# Power_MPU.net
KiCad netlist of a schematic drawn in Altium Designer
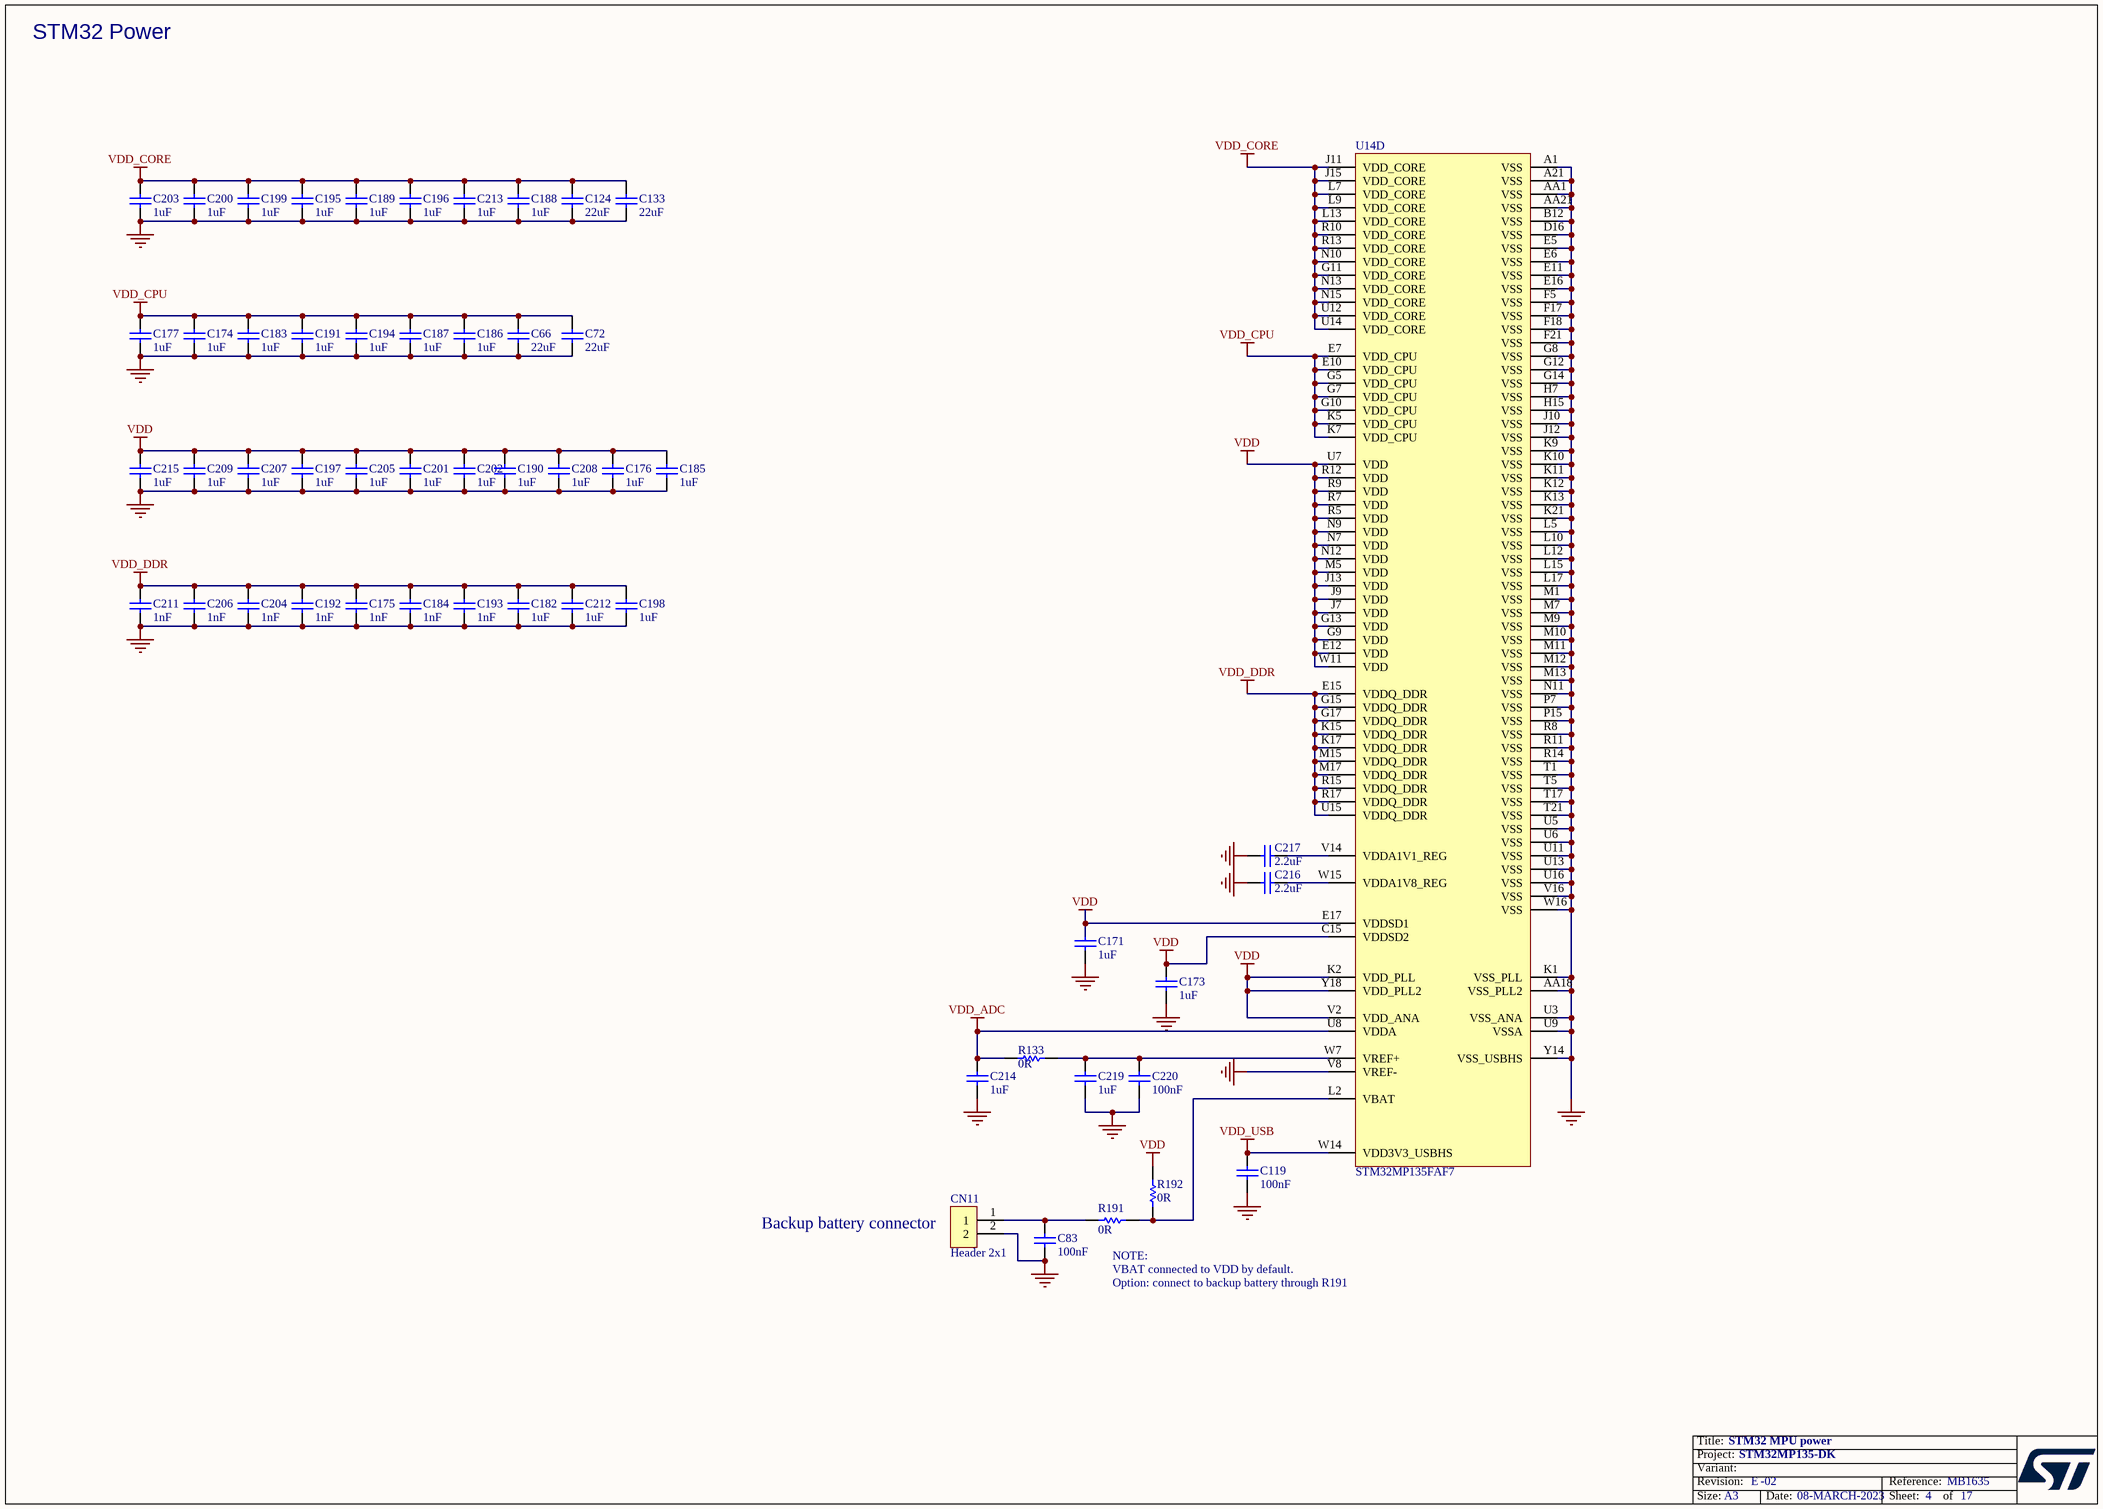
[diagram p0: Power_MPU.SchDoc]

(export (version "E")
  (design (tool "Eeschema 10.0.6"))
  (components
    (comp (ref "C66")
      (value "22uF")
      (footprint "C0603")
      (description "Capacitor, MLCC, 22uF, 6V3, X5R, +/-20%, 0603, T=0.8mm")
      (fields (field (name "INTERNAL_PART_NUMBER") "MCD-00100") (field (name "MANUFACTURER") "MURATA"))
      (libsource (lib "MCD_PARTS_database") (part "Capacitor"))
    )
    (comp (ref "C72")
      (value "22uF")
      (footprint "C0603")
      (description "Capacitor, MLCC, 22uF, 6V3, X5R, +/-20%, 0603, T=0.8mm")
      (fields (field (name "INTERNAL_PART_NUMBER") "MCD-00100") (field (name "MANUFACTURER") "MURATA"))
      (libsource (lib "MCD_PARTS_database") (part "Capacitor"))
    )
    (comp (ref "C83")
      (value "100nF")
      (footprint "C0402")
      (description "Capacitor, MLCC, 100nF, 16V, X7R, +/-10%, 0402, T=0.5mm")
      (fields
        (field (name "INTERNAL_PART_NUMBER") "MCD-00006")
        (field (name "MANUFACTURER_PART_NUMBER") "CC0402KRX7R7BB104")
      )
      (libsource (lib "MCD_PARTS_database") (part "Capacitor"))
    )
    (comp (ref "C119")
      (value "100nF")
      (footprint "C0402")
      (description "Capacitor, MLCC, 100nF, 16V, X7R, +/-10%, 0402, T=0.5mm")
      (fields
        (field (name "INTERNAL_PART_NUMBER") "MCD-00006")
        (field (name "MANUFACTURER_PART_NUMBER") "CC0402KRX7R7BB104")
      )
      (libsource (lib "MCD_PARTS_database") (part "Capacitor"))
    )
    (comp (ref "C124")
      (value "22uF")
      (footprint "C0603")
      (description "Capacitor, MLCC, 22uF, 6V3, X5R, +/-20%, 0603, T=0.8mm")
      (fields (field (name "INTERNAL_PART_NUMBER") "MCD-00100") (field (name "MANUFACTURER") "MURATA"))
      (libsource (lib "MCD_PARTS_database") (part "Capacitor"))
    )
    (comp (ref "C133")
      (value "22uF")
      (footprint "C0603")
      (description "Capacitor, MLCC, 22uF, 6V3, X5R, +/-20%, 0603, T=0.8mm")
      (fields (field (name "INTERNAL_PART_NUMBER") "MCD-00100") (field (name "MANUFACTURER") "MURATA"))
      (libsource (lib "MCD_PARTS_database") (part "Capacitor"))
    )
    (comp (ref "C171")
      (value "1uF")
      (footprint "C0201_MURATA_GRM033_H0P3")
      (description "Capacitor, MLCC, 1uF, 6.3V, X5R, +/-20%, 0201, T=0,3mm")
      (fields (field (name "INTERNAL_PART_NUMBER") "MCD-02377") (field (name "MANUFACTURER") "MURATA"))
      (libsource (lib "MCD_PARTS_database") (part "Capacitor"))
    )
    (comp (ref "C173")
      (value "1uF")
      (footprint "C0201_MURATA_GRM033_H0P3")
      (description "Capacitor, MLCC, 1uF, 6.3V, X5R, +/-20%, 0201, T=0,3mm")
      (fields (field (name "INTERNAL_PART_NUMBER") "MCD-02377") (field (name "MANUFACTURER") "MURATA"))
      (libsource (lib "MCD_PARTS_database") (part "Capacitor"))
    )
    (comp (ref "C174")
      (value "1uF")
      (footprint "C0201_MURATA_GRM033_H0P3")
      (description "Capacitor, MLCC, 1uF, 6.3V, X5R, +/-20%, 0201, T=0,3mm")
      (fields (field (name "INTERNAL_PART_NUMBER") "MCD-02377") (field (name "MANUFACTURER") "MURATA"))
      (libsource (lib "MCD_PARTS_database") (part "Capacitor"))
    )
    (comp (ref "C175")
      (value "1nF")
      (footprint "C0201_MURATA_GRM033_H0P3")
      (description "Capacitor, MLCC, 1nF, 25V, X7R,+/-5%, 0201,T=0.3mm")
      (fields (field (name "INTERNAL_PART_NUMBER") "MCD-01729") (field (name "MANUFACTURER") "MURATA"))
      (libsource (lib "MCD_PARTS_database") (part "Capacitor"))
    )
    (comp (ref "C176")
      (value "1uF")
      (footprint "C0201_MURATA_GRM033_H0P3")
      (description "Capacitor, MLCC, 1uF, 6.3V, X5R, +/-20%, 0201, T=0,3mm")
      (fields (field (name "INTERNAL_PART_NUMBER") "MCD-02377") (field (name "MANUFACTURER") "MURATA"))
      (libsource (lib "MCD_PARTS_database") (part "Capacitor"))
    )
    (comp (ref "C177")
      (value "1uF")
      (footprint "C0201_MURATA_GRM033_H0P3")
      (description "Capacitor, MLCC, 1uF, 6.3V, X5R, +/-20%, 0201, T=0,3mm")
      (fields (field (name "INTERNAL_PART_NUMBER") "MCD-02377") (field (name "MANUFACTURER") "MURATA"))
      (libsource (lib "MCD_PARTS_database") (part "Capacitor"))
    )
    (comp (ref "C182")
      (value "1uF")
      (footprint "C0201_MURATA_GRM033_H0P3")
      (description "Capacitor, MLCC, 1uF, 6.3V, X5R, +/-20%, 0201, T=0,3mm")
      (fields (field (name "INTERNAL_PART_NUMBER") "MCD-02377") (field (name "MANUFACTURER") "MURATA"))
      (libsource (lib "MCD_PARTS_database") (part "Capacitor"))
    )
    (comp (ref "C183")
      (value "1uF")
      (footprint "C0201_MURATA_GRM033_H0P3")
      (description "Capacitor, MLCC, 1uF, 6.3V, X5R, +/-20%, 0201, T=0,3mm")
      (fields (field (name "INTERNAL_PART_NUMBER") "MCD-02377") (field (name "MANUFACTURER") "MURATA"))
      (libsource (lib "MCD_PARTS_database") (part "Capacitor"))
    )
    (comp (ref "C184")
      (value "1nF")
      (footprint "C0201_MURATA_GRM033_H0P3")
      (description "Capacitor, MLCC, 1nF, 25V, X7R,+/-5%, 0201,T=0.3mm")
      (fields (field (name "INTERNAL_PART_NUMBER") "MCD-01729") (field (name "MANUFACTURER") "MURATA"))
      (libsource (lib "MCD_PARTS_database") (part "Capacitor"))
    )
    (comp (ref "C185")
      (value "1uF")
      (footprint "C0201_MURATA_GRM033_H0P3")
      (description "Capacitor, MLCC, 1uF, 6.3V, X5R, +/-20%, 0201, T=0,3mm")
      (fields (field (name "INTERNAL_PART_NUMBER") "MCD-02377") (field (name "MANUFACTURER") "MURATA"))
      (libsource (lib "MCD_PARTS_database") (part "Capacitor"))
    )
    (comp (ref "C186")
      (value "1uF")
      (footprint "C0201_MURATA_GRM033_H0P3")
      (description "Capacitor, MLCC, 1uF, 6.3V, X5R, +/-20%, 0201, T=0,3mm")
      (fields (field (name "INTERNAL_PART_NUMBER") "MCD-02377") (field (name "MANUFACTURER") "MURATA"))
      (libsource (lib "MCD_PARTS_database") (part "Capacitor"))
    )
    (comp (ref "C187")
      (value "1uF")
      (footprint "C0201_MURATA_GRM033_H0P3")
      (description "Capacitor, MLCC, 1uF, 6.3V, X5R, +/-20%, 0201, T=0,3mm")
      (fields (field (name "INTERNAL_PART_NUMBER") "MCD-02377") (field (name "MANUFACTURER") "MURATA"))
      (libsource (lib "MCD_PARTS_database") (part "Capacitor"))
    )
    (comp (ref "C188")
      (value "1uF")
      (footprint "C0201_MURATA_GRM033_H0P3")
      (description "Capacitor, MLCC, 1uF, 6.3V, X5R, +/-20%, 0201, T=0,3mm")
      (fields (field (name "INTERNAL_PART_NUMBER") "MCD-02377") (field (name "MANUFACTURER") "MURATA"))
      (libsource (lib "MCD_PARTS_database") (part "Capacitor"))
    )
    (comp (ref "C189")
      (value "1uF")
      (footprint "C0201_MURATA_GRM033_H0P3")
      (description "Capacitor, MLCC, 1uF, 6.3V, X5R, +/-20%, 0201, T=0,3mm")
      (fields (field (name "INTERNAL_PART_NUMBER") "MCD-02377") (field (name "MANUFACTURER") "MURATA"))
      (libsource (lib "MCD_PARTS_database") (part "Capacitor"))
    )
    (comp (ref "C190")
      (value "1uF")
      (footprint "C0201_MURATA_GRM033_H0P3")
      (description "Capacitor, MLCC, 1uF, 6.3V, X5R, +/-20%, 0201, T=0,3mm")
      (fields (field (name "INTERNAL_PART_NUMBER") "MCD-02377") (field (name "MANUFACTURER") "MURATA"))
      (libsource (lib "MCD_PARTS_database") (part "Capacitor"))
    )
    (comp (ref "C191")
      (value "1uF")
      (footprint "C0201_MURATA_GRM033_H0P3")
      (description "Capacitor, MLCC, 1uF, 6.3V, X5R, +/-20%, 0201, T=0,3mm")
      (fields (field (name "INTERNAL_PART_NUMBER") "MCD-02377") (field (name "MANUFACTURER") "MURATA"))
      (libsource (lib "MCD_PARTS_database") (part "Capacitor"))
    )
    (comp (ref "C192")
      (value "1nF")
      (footprint "C0201_MURATA_GRM033_H0P3")
      (description "Capacitor, MLCC, 1nF, 25V, X7R,+/-5%, 0201,T=0.3mm")
      (fields (field (name "INTERNAL_PART_NUMBER") "MCD-01729") (field (name "MANUFACTURER") "MURATA"))
      (libsource (lib "MCD_PARTS_database") (part "Capacitor"))
    )
    (comp (ref "C193")
      (value "1nF")
      (footprint "C0201_MURATA_GRM033_H0P3")
      (description "Capacitor, MLCC, 1nF, 25V, X7R,+/-5%, 0201,T=0.3mm")
      (fields (field (name "INTERNAL_PART_NUMBER") "MCD-01729") (field (name "MANUFACTURER") "MURATA"))
      (libsource (lib "MCD_PARTS_database") (part "Capacitor"))
    )
    (comp (ref "C194")
      (value "1uF")
      (footprint "C0201_MURATA_GRM033_H0P3")
      (description "Capacitor, MLCC, 1uF, 6.3V, X5R, +/-20%, 0201, T=0,3mm")
      (fields (field (name "INTERNAL_PART_NUMBER") "MCD-02377") (field (name "MANUFACTURER") "MURATA"))
      (libsource (lib "MCD_PARTS_database") (part "Capacitor"))
    )
    (comp (ref "C195")
      (value "1uF")
      (footprint "C0201_MURATA_GRM033_H0P3")
      (description "Capacitor, MLCC, 1uF, 6.3V, X5R, +/-20%, 0201, T=0,3mm")
      (fields (field (name "INTERNAL_PART_NUMBER") "MCD-02377") (field (name "MANUFACTURER") "MURATA"))
      (libsource (lib "MCD_PARTS_database") (part "Capacitor"))
    )
    (comp (ref "C196")
      (value "1uF")
      (footprint "C0201_MURATA_GRM033_H0P3")
      (description "Capacitor, MLCC, 1uF, 6.3V, X5R, +/-20%, 0201, T=0,3mm")
      (fields (field (name "INTERNAL_PART_NUMBER") "MCD-02377") (field (name "MANUFACTURER") "MURATA"))
      (libsource (lib "MCD_PARTS_database") (part "Capacitor"))
    )
    (comp (ref "C197")
      (value "1uF")
      (footprint "C0201_MURATA_GRM033_H0P3")
      (description "Capacitor, MLCC, 1uF, 6.3V, X5R, +/-20%, 0201, T=0,3mm")
      (fields (field (name "INTERNAL_PART_NUMBER") "MCD-02377") (field (name "MANUFACTURER") "MURATA"))
      (libsource (lib "MCD_PARTS_database") (part "Capacitor"))
    )
    (comp (ref "C198")
      (value "1uF")
      (footprint "C0201_MURATA_GRM033_H0P3")
      (description "Capacitor, MLCC, 1uF, 6.3V, X5R, +/-20%, 0201, T=0,3mm")
      (fields (field (name "INTERNAL_PART_NUMBER") "MCD-02377") (field (name "MANUFACTURER") "MURATA"))
      (libsource (lib "MCD_PARTS_database") (part "Capacitor"))
    )
    (comp (ref "C199")
      (value "1uF")
      (footprint "C0201_MURATA_GRM033_H0P3")
      (description "Capacitor, MLCC, 1uF, 6.3V, X5R, +/-20%, 0201, T=0,3mm")
      (fields (field (name "INTERNAL_PART_NUMBER") "MCD-02377") (field (name "MANUFACTURER") "MURATA"))
      (libsource (lib "MCD_PARTS_database") (part "Capacitor"))
    )
    (comp (ref "C200")
      (value "1uF")
      (footprint "C0201_MURATA_GRM033_H0P3")
      (description "Capacitor, MLCC, 1uF, 6.3V, X5R, +/-20%, 0201, T=0,3mm")
      (fields (field (name "INTERNAL_PART_NUMBER") "MCD-02377") (field (name "MANUFACTURER") "MURATA"))
      (libsource (lib "MCD_PARTS_database") (part "Capacitor"))
    )
    (comp (ref "C201")
      (value "1uF")
      (footprint "C0201_MURATA_GRM033_H0P3")
      (description "Capacitor, MLCC, 1uF, 6.3V, X5R, +/-20%, 0201, T=0,3mm")
      (fields (field (name "INTERNAL_PART_NUMBER") "MCD-02377") (field (name "MANUFACTURER") "MURATA"))
      (libsource (lib "MCD_PARTS_database") (part "Capacitor"))
    )
    (comp (ref "C202")
      (value "1uF")
      (footprint "C0201_MURATA_GRM033_H0P3")
      (description "Capacitor, MLCC, 1uF, 6.3V, X5R, +/-20%, 0201, T=0,3mm")
      (fields (field (name "INTERNAL_PART_NUMBER") "MCD-02377") (field (name "MANUFACTURER") "MURATA"))
      (libsource (lib "MCD_PARTS_database") (part "Capacitor"))
    )
    (comp (ref "C203")
      (value "1uF")
      (footprint "C0201_MURATA_GRM033_H0P3")
      (description "Capacitor, MLCC, 1uF, 6.3V, X5R, +/-20%, 0201, T=0,3mm")
      (fields (field (name "INTERNAL_PART_NUMBER") "MCD-02377") (field (name "MANUFACTURER") "MURATA"))
      (libsource (lib "MCD_PARTS_database") (part "Capacitor"))
    )
    (comp (ref "C204")
      (value "1nF")
      (footprint "C0201_MURATA_GRM033_H0P3")
      (description "Capacitor, MLCC, 1nF, 25V, X7R,+/-5%, 0201,T=0.3mm")
      (fields (field (name "INTERNAL_PART_NUMBER") "MCD-01729") (field (name "MANUFACTURER") "MURATA"))
      (libsource (lib "MCD_PARTS_database") (part "Capacitor"))
    )
    (comp (ref "C205")
      (value "1uF")
      (footprint "C0201_MURATA_GRM033_H0P3")
      (description "Capacitor, MLCC, 1uF, 6.3V, X5R, +/-20%, 0201, T=0,3mm")
      (fields (field (name "INTERNAL_PART_NUMBER") "MCD-02377") (field (name "MANUFACTURER") "MURATA"))
      (libsource (lib "MCD_PARTS_database") (part "Capacitor"))
    )
    (comp (ref "C206")
      (value "1nF")
      (footprint "C0201_MURATA_GRM033_H0P3")
      (description "Capacitor, MLCC, 1nF, 25V, X7R,+/-5%, 0201,T=0.3mm")
      (fields (field (name "INTERNAL_PART_NUMBER") "MCD-01729") (field (name "MANUFACTURER") "MURATA"))
      (libsource (lib "MCD_PARTS_database") (part "Capacitor"))
    )
    (comp (ref "C207")
      (value "1uF")
      (footprint "C0201_MURATA_GRM033_H0P3")
      (description "Capacitor, MLCC, 1uF, 6.3V, X5R, +/-20%, 0201, T=0,3mm")
      (fields (field (name "INTERNAL_PART_NUMBER") "MCD-02377") (field (name "MANUFACTURER") "MURATA"))
      (libsource (lib "MCD_PARTS_database") (part "Capacitor"))
    )
    (comp (ref "C208")
      (value "1uF")
      (footprint "C0201_MURATA_GRM033_H0P3")
      (description "Capacitor, MLCC, 1uF, 6.3V, X5R, +/-20%, 0201, T=0,3mm")
      (fields (field (name "INTERNAL_PART_NUMBER") "MCD-02377") (field (name "MANUFACTURER") "MURATA"))
      (libsource (lib "MCD_PARTS_database") (part "Capacitor"))
    )
    (comp (ref "C209")
      (value "1uF")
      (footprint "C0201_MURATA_GRM033_H0P3")
      (description "Capacitor, MLCC, 1uF, 6.3V, X5R, +/-20%, 0201, T=0,3mm")
      (fields (field (name "INTERNAL_PART_NUMBER") "MCD-02377") (field (name "MANUFACTURER") "MURATA"))
      (libsource (lib "MCD_PARTS_database") (part "Capacitor"))
    )
    (comp (ref "C211")
      (value "1nF")
      (footprint "C0201_MURATA_GRM033_H0P3")
      (description "Capacitor, MLCC, 1nF, 25V, X7R,+/-5%, 0201,T=0.3mm")
      (fields (field (name "INTERNAL_PART_NUMBER") "MCD-01729") (field (name "MANUFACTURER") "MURATA"))
      (libsource (lib "MCD_PARTS_database") (part "Capacitor"))
    )
    (comp (ref "C212")
      (value "1uF")
      (footprint "C0201_MURATA_GRM033_H0P3")
      (description "Capacitor, MLCC, 1uF, 6.3V, X5R, +/-20%, 0201, T=0,3mm")
      (fields (field (name "INTERNAL_PART_NUMBER") "MCD-02377") (field (name "MANUFACTURER") "MURATA"))
      (libsource (lib "MCD_PARTS_database") (part "Capacitor"))
    )
    (comp (ref "C213")
      (value "1uF")
      (footprint "C0201_MURATA_GRM033_H0P3")
      (description "Capacitor, MLCC, 1uF, 6.3V, X5R, +/-20%, 0201, T=0,3mm")
      (fields (field (name "INTERNAL_PART_NUMBER") "MCD-02377") (field (name "MANUFACTURER") "MURATA"))
      (libsource (lib "MCD_PARTS_database") (part "Capacitor"))
    )
    (comp (ref "C214")
      (value "1uF")
      (footprint "C0201_MURATA_GRM033_H0P3")
      (description "Capacitor, MLCC, 1uF, 6.3V, X5R, +/-20%, 0201, T=0,3mm")
      (fields (field (name "INTERNAL_PART_NUMBER") "MCD-02377") (field (name "MANUFACTURER") "MURATA"))
      (libsource (lib "MCD_PARTS_database") (part "Capacitor"))
    )
    (comp (ref "C215")
      (value "1uF")
      (footprint "C0201_MURATA_GRM033_H0P3")
      (description "Capacitor, MLCC, 1uF, 6.3V, X5R, +/-20%, 0201, T=0,3mm")
      (fields (field (name "INTERNAL_PART_NUMBER") "MCD-02377") (field (name "MANUFACTURER") "MURATA"))
      (libsource (lib "MCD_PARTS_database") (part "Capacitor"))
    )
    (comp (ref "C216")
      (value "2.2uF")
      (footprint "C0201_H0P5")
      (description "Capacitor, MLCC, 2.2uF, 10V, X5R,+/-10%, 0201, T=0.5mm")
      (fields
        (field (name "INTERNAL_PART_NUMBER") "MCD-02235")
        (field (name "MANUFACTURER_PART_NUMBER") "GRM033R61A225KE47D")
      )
      (libsource (lib "MCD_PARTS_database") (part "Capacitor"))
    )
    (comp (ref "C217")
      (value "2.2uF")
      (footprint "C0201_H0P5")
      (description "Capacitor, MLCC, 2.2uF, 10V, X5R,+/-10%, 0201, T=0.5mm")
      (fields
        (field (name "INTERNAL_PART_NUMBER") "MCD-02235")
        (field (name "MANUFACTURER_PART_NUMBER") "GRM033R61A225KE47D")
      )
      (libsource (lib "MCD_PARTS_database") (part "Capacitor"))
    )
    (comp (ref "C219")
      (value "1uF")
      (footprint "C0201_MURATA_GRM033_H0P3")
      (description "Capacitor, MLCC, 1uF, 6.3V, X5R, +/-20%, 0201, T=0,3mm")
      (fields (field (name "INTERNAL_PART_NUMBER") "MCD-02377") (field (name "MANUFACTURER") "MURATA"))
      (libsource (lib "MCD_PARTS_database") (part "Capacitor"))
    )
    (comp (ref "C220")
      (value "100nF")
      (footprint "C0402")
      (description "Capacitor, MLCC, 100nF, 16V, X7R, +/-10%, 0402, T=0.5mm")
      (fields
        (field (name "INTERNAL_PART_NUMBER") "MCD-00006")
        (field (name "MANUFACTURER_PART_NUMBER") "CC0402KRX7R7BB104")
      )
      (libsource (lib "MCD_PARTS_database") (part "Capacitor"))
    )
    (comp (ref "CN11")
      (value "Header 2x1")
      (footprint "CON_MOLEX_53047-0210")
      (description "Header, 2x1, 1.25mm, VR, TH, T=2.25mm/2.3mm")
      (fields
        (field (name "INTERNAL_PART_NUMBER") "MCD-00655")
        (field (name "MANUFACTURER_PART_NUMBER") "53047-0210")
      )
      (libsource (lib "MCD_PARTS_database") (part "Header 2x1"))
    )
    (comp (ref "R133")
      (value "0R")
      (footprint "R0402")
      (description "Resistor, 0R, 0402, +/-5%, 1/16W")
      (fields
        (field (name "INTERNAL_PART_NUMBER") "MCD-00052")
        (field (name "MANUFACTURER_PART_NUMBER") "RC0402JR-070RL")
      )
      (libsource (lib "MCD_PARTS_database") (part "Resistor"))
    )
    (comp (ref "R191")
      (value "0R")
      (footprint "R0402")
      (description "Resistor, 0R, 0402, +/-5%, 1/16W")
      (fields
        (field (name "INTERNAL_PART_NUMBER") "MCD-00052")
        (field (name "MANUFACTURER_PART_NUMBER") "RC0402JR-070RL")
      )
      (libsource (lib "MCD_PARTS_database") (part "Resistor"))
    )
    (comp (ref "R192")
      (value "0R")
      (footprint "R0402")
      (description "Resistor, 0R, 0402, +/-5%, 1/16W")
      (fields
        (field (name "INTERNAL_PART_NUMBER") "MCD-00052")
        (field (name "MANUFACTURER_PART_NUMBER") "RC0402JR-070RL")
      )
      (libsource (lib "MCD_PARTS_database") (part "Resistor"))
    )
    (comp (ref "U14")
      (value "STM32MP135FAF7")
      (footprint "ICC_TFBGA320_11X11_STM32MP135FA7_P050_H1P20")
      (fields
        (field (name "INTERNAL_PART_NUMBER") "MCD-02251")
        (field (name "MANUFACTURER") "STMICROELECTRONICS")
      )
      (libsource (lib "MCD_PARTS_database") (part "STM32MP135FAF7"))
    )
  )
  (nets
    (net (code "1") (name "GND") (class "Default")
      (node (ref "C119") (pin "1") (pinfunction "1_1") (pintype "passive"))
      (node (ref "C124") (pin "1") (pinfunction "1_1") (pintype "passive"))
      (node (ref "C133") (pin "1") (pinfunction "1_1") (pintype "passive"))
      (node (ref "C171") (pin "1") (pinfunction "1_1") (pintype "passive"))
      (node (ref "C173") (pin "1") (pinfunction "1_1") (pintype "passive"))
      (node (ref "C174") (pin "1") (pinfunction "1_1") (pintype "passive"))
      (node (ref "C175") (pin "1") (pinfunction "1_1") (pintype "passive"))
      (node (ref "C176") (pin "1") (pinfunction "1_1") (pintype "passive"))
      (node (ref "C177") (pin "2") (pinfunction "2_2") (pintype "passive"))
      (node (ref "C182") (pin "1") (pinfunction "1_1") (pintype "passive"))
      (node (ref "C183") (pin "1") (pinfunction "1_1") (pintype "passive"))
      (node (ref "C184") (pin "1") (pinfunction "1_1") (pintype "passive"))
      (node (ref "C185") (pin "2") (pinfunction "2_2") (pintype "passive"))
      (node (ref "C186") (pin "1") (pinfunction "1_1") (pintype "passive"))
      (node (ref "C187") (pin "1") (pinfunction "1_1") (pintype "passive"))
      (node (ref "C188") (pin "1") (pinfunction "1_1") (pintype "passive"))
      (node (ref "C189") (pin "1") (pinfunction "1_1") (pintype "passive"))
      (node (ref "C190") (pin "1") (pinfunction "1_1") (pintype "passive"))
      (node (ref "C191") (pin "2") (pinfunction "2_2") (pintype "passive"))
      (node (ref "C192") (pin "1") (pinfunction "1_1") (pintype "passive"))
      (node (ref "C193") (pin "1") (pinfunction "1_1") (pintype "passive"))
      (node (ref "C194") (pin "1") (pinfunction "1_1") (pintype "passive"))
      (node (ref "C195") (pin "2") (pinfunction "2_2") (pintype "passive"))
      (node (ref "C196") (pin "1") (pinfunction "1_1") (pintype "passive"))
      (node (ref "C197") (pin "1") (pinfunction "1_1") (pintype "passive"))
      (node (ref "C198") (pin "1") (pinfunction "1_1") (pintype "passive"))
      (node (ref "C199") (pin "1") (pinfunction "1_1") (pintype "passive"))
      (node (ref "C200") (pin "1") (pinfunction "1_1") (pintype "passive"))
      (node (ref "C201") (pin "1") (pinfunction "1_1") (pintype "passive"))
      (node (ref "C202") (pin "1") (pinfunction "1_1") (pintype "passive"))
      (node (ref "C203") (pin "2") (pinfunction "2_2") (pintype "passive"))
      (node (ref "C204") (pin "2") (pinfunction "2_2") (pintype "passive"))
      (node (ref "C205") (pin "1") (pinfunction "1_1") (pintype "passive"))
      (node (ref "C206") (pin "1") (pinfunction "1_1") (pintype "passive"))
      (node (ref "C207") (pin "2") (pinfunction "2_2") (pintype "passive"))
      (node (ref "C208") (pin "1") (pinfunction "1_1") (pintype "passive"))
      (node (ref "C209") (pin "1") (pinfunction "1_1") (pintype "passive"))
      (node (ref "C211") (pin "1") (pinfunction "1_1") (pintype "passive"))
      (node (ref "C212") (pin "1") (pinfunction "1_1") (pintype "passive"))
      (node (ref "C213") (pin "1") (pinfunction "1_1") (pintype "passive"))
      (node (ref "C214") (pin "2") (pinfunction "2_2") (pintype "passive"))
      (node (ref "C215") (pin "2") (pinfunction "2_2") (pintype "passive"))
      (node (ref "C216") (pin "2") (pinfunction "2_2") (pintype "passive"))
      (node (ref "C217") (pin "2") (pinfunction "2_2") (pintype "passive"))
      (node (ref "C219") (pin "2") (pinfunction "2_2") (pintype "passive"))
      (node (ref "C220") (pin "1") (pinfunction "1_1") (pintype "passive"))
      (node (ref "C66") (pin "1") (pinfunction "1_1") (pintype "passive"))
      (node (ref "C72") (pin "1") (pinfunction "1_1") (pintype "passive"))
      (node (ref "C83") (pin "1") (pinfunction "1_1") (pintype "passive"))
      (node (ref "CN11") (pin "2") (pinfunction "2_2") (pintype "passive"))
      (node (ref "U14") (pin "A1") (pinfunction "VSS_A1") (pintype "passive"))
      (node (ref "U14") (pin "A21") (pinfunction "VSS_A21") (pintype "passive"))
      (node (ref "U14") (pin "AA1") (pinfunction "VSS_AA1") (pintype "passive"))
      (node (ref "U14") (pin "AA18") (pinfunction "VSS_PLL2_AA18") (pintype "passive"))
      (node (ref "U14") (pin "AA21") (pinfunction "VSS_AA21") (pintype "passive"))
      (node (ref "U14") (pin "B12") (pinfunction "VSS_B12") (pintype "passive"))
      (node (ref "U14") (pin "D16") (pinfunction "VSS_D16") (pintype "passive"))
      (node (ref "U14") (pin "E11") (pinfunction "VSS_E11") (pintype "passive"))
      (node (ref "U14") (pin "E16") (pinfunction "VSS_E16") (pintype "passive"))
      (node (ref "U14") (pin "E5") (pinfunction "VSS_E5") (pintype "passive"))
      (node (ref "U14") (pin "E6") (pinfunction "VSS_E6") (pintype "passive"))
      (node (ref "U14") (pin "F17") (pinfunction "VSS_F17") (pintype "passive"))
      (node (ref "U14") (pin "F18") (pinfunction "VSS_F18") (pintype "passive"))
      (node (ref "U14") (pin "F21") (pinfunction "VSS_F21") (pintype "passive"))
      (node (ref "U14") (pin "F5") (pinfunction "VSS_F5") (pintype "passive"))
      (node (ref "U14") (pin "G12") (pinfunction "VSS_G12") (pintype "passive"))
      (node (ref "U14") (pin "G14") (pinfunction "VSS_G14") (pintype "passive"))
      (node (ref "U14") (pin "G8") (pinfunction "VSS_G8") (pintype "passive"))
      (node (ref "U14") (pin "H15") (pinfunction "VSS_H15") (pintype "passive"))
      (node (ref "U14") (pin "H7") (pinfunction "VSS_H7") (pintype "passive"))
      (node (ref "U14") (pin "J10") (pinfunction "VSS_J10") (pintype "passive"))
      (node (ref "U14") (pin "J12") (pinfunction "VSS_J12") (pintype "passive"))
      (node (ref "U14") (pin "K1") (pinfunction "VSS_PLL_K1") (pintype "passive"))
      (node (ref "U14") (pin "K10") (pinfunction "VSS_K10") (pintype "passive"))
      (node (ref "U14") (pin "K11") (pinfunction "VSS_K11") (pintype "passive"))
      (node (ref "U14") (pin "K12") (pinfunction "VSS_K12") (pintype "passive"))
      (node (ref "U14") (pin "K13") (pinfunction "VSS_K13") (pintype "passive"))
      (node (ref "U14") (pin "K21") (pinfunction "VSS_K21") (pintype "passive"))
      (node (ref "U14") (pin "K9") (pinfunction "VSS_K9") (pintype "passive"))
      (node (ref "U14") (pin "L10") (pinfunction "VSS_L10") (pintype "passive"))
      (node (ref "U14") (pin "L12") (pinfunction "VSS_L12") (pintype "passive"))
      (node (ref "U14") (pin "L15") (pinfunction "VSS_L15") (pintype "passive"))
      (node (ref "U14") (pin "L17") (pinfunction "VSS_L17") (pintype "passive"))
      (node (ref "U14") (pin "L5") (pinfunction "VSS_L5") (pintype "passive"))
      (node (ref "U14") (pin "M1") (pinfunction "VSS_M1") (pintype "passive"))
      (node (ref "U14") (pin "M10") (pinfunction "VSS_M10") (pintype "passive"))
      (node (ref "U14") (pin "M11") (pinfunction "VSS_M11") (pintype "passive"))
      (node (ref "U14") (pin "M12") (pinfunction "VSS_M12") (pintype "passive"))
      (node (ref "U14") (pin "M13") (pinfunction "VSS_M13") (pintype "passive"))
      (node (ref "U14") (pin "M7") (pinfunction "VSS_M7") (pintype "passive"))
      (node (ref "U14") (pin "M9") (pinfunction "VSS_M9") (pintype "passive"))
      (node (ref "U14") (pin "N11") (pinfunction "VSS_N11") (pintype "passive"))
      (node (ref "U14") (pin "P15") (pinfunction "VSS_P15") (pintype "passive"))
      (node (ref "U14") (pin "P7") (pinfunction "VSS_P7") (pintype "passive"))
      (node (ref "U14") (pin "R11") (pinfunction "VSS_R11") (pintype "passive"))
      (node (ref "U14") (pin "R14") (pinfunction "VSS_R14") (pintype "passive"))
      (node (ref "U14") (pin "R8") (pinfunction "VSS_R8") (pintype "passive"))
      (node (ref "U14") (pin "T1") (pinfunction "VSS_T1") (pintype "passive"))
      (node (ref "U14") (pin "T17") (pinfunction "VSS_T17") (pintype "passive"))
      (node (ref "U14") (pin "T21") (pinfunction "VSS_T21") (pintype "passive"))
      (node (ref "U14") (pin "T5") (pinfunction "VSS_T5") (pintype "passive"))
      (node (ref "U14") (pin "U11") (pinfunction "VSS_U11") (pintype "passive"))
      (node (ref "U14") (pin "U13") (pinfunction "VSS_U13") (pintype "passive"))
      (node (ref "U14") (pin "U16") (pinfunction "VSS_U16") (pintype "passive"))
      (node (ref "U14") (pin "U3") (pinfunction "VSS_ANA_U3") (pintype "passive"))
      (node (ref "U14") (pin "U5") (pinfunction "VSS_U5") (pintype "passive"))
      (node (ref "U14") (pin "U6") (pinfunction "VSS_U6") (pintype "passive"))
      (node (ref "U14") (pin "U9") (pinfunction "VSSA_U9") (pintype "passive"))
      (node (ref "U14") (pin "V16") (pinfunction "VSS_V16") (pintype "passive"))
      (node (ref "U14") (pin "V8") (pinfunction "VREF-_V8") (pintype "passive"))
      (node (ref "U14") (pin "W16") (pinfunction "VSS_W16") (pintype "passive"))
      (node (ref "U14") (pin "Y14") (pinfunction "VSS_USBHS_Y14") (pintype "passive"))
    )
    (net (code "2") (name "Net-(C83-Pad2)") (class "Default")
      (node (ref "C83") (pin "2") (pinfunction "2_2") (pintype "passive"))
      (node (ref "CN11") (pin "1") (pinfunction "1_1") (pintype "passive"))
      (node (ref "R191") (pin "2") (pinfunction "2_2") (pintype "passive"))
    )
    (net (code "3") (name "Net-(U14D-VBAT)") (class "Default")
      (node (ref "R191") (pin "1") (pinfunction "1_1") (pintype "passive"))
      (node (ref "R192") (pin "1") (pinfunction "1_1") (pintype "passive"))
      (node (ref "U14") (pin "L2") (pinfunction "VBAT_L2") (pintype "passive"))
    )
    (net (code "4") (name "Net-(U14D-VDDA1V1_REG)") (class "Default")
      (node (ref "C217") (pin "1") (pinfunction "1_1") (pintype "passive"))
      (node (ref "U14") (pin "V14") (pinfunction "VDDA1V1_REG_V14") (pintype "passive"))
    )
    (net (code "5") (name "Net-(U14D-VDDA1V8_REG)") (class "Default")
      (node (ref "C216") (pin "1") (pinfunction "1_1") (pintype "passive"))
      (node (ref "U14") (pin "W15") (pinfunction "VDDA1V8_REG_W15") (pintype "passive"))
    )
    (net (code "6") (name "Net-(U14D-VREF+)") (class "Default")
      (node (ref "C219") (pin "1") (pinfunction "1_1") (pintype "passive"))
      (node (ref "C220") (pin "2") (pinfunction "2_2") (pintype "passive"))
      (node (ref "R133") (pin "1") (pinfunction "1_1") (pintype "passive"))
      (node (ref "U14") (pin "W7") (pinfunction "VREF+_W7") (pintype "passive"))
    )
    (net (code "7") (name "VDD") (class "Default")
      (node (ref "C171") (pin "2") (pinfunction "2_2") (pintype "passive"))
      (node (ref "C173") (pin "2") (pinfunction "2_2") (pintype "passive"))
      (node (ref "C176") (pin "2") (pinfunction "2_2") (pintype "passive"))
      (node (ref "C185") (pin "1") (pinfunction "1_1") (pintype "passive"))
      (node (ref "C190") (pin "2") (pinfunction "2_2") (pintype "passive"))
      (node (ref "C197") (pin "2") (pinfunction "2_2") (pintype "passive"))
      (node (ref "C201") (pin "2") (pinfunction "2_2") (pintype "passive"))
      (node (ref "C202") (pin "2") (pinfunction "2_2") (pintype "passive"))
      (node (ref "C205") (pin "2") (pinfunction "2_2") (pintype "passive"))
      (node (ref "C207") (pin "1") (pinfunction "1_1") (pintype "passive"))
      (node (ref "C208") (pin "2") (pinfunction "2_2") (pintype "passive"))
      (node (ref "C209") (pin "2") (pinfunction "2_2") (pintype "passive"))
      (node (ref "C215") (pin "1") (pinfunction "1_1") (pintype "passive"))
      (node (ref "R192") (pin "2") (pinfunction "2_2") (pintype "passive"))
      (node (ref "U14") (pin "C15") (pinfunction "VDDSD2_C15") (pintype "passive"))
      (node (ref "U14") (pin "E12") (pinfunction "VDD_E12") (pintype "passive"))
      (node (ref "U14") (pin "E17") (pinfunction "VDDSD1_E17") (pintype "passive"))
      (node (ref "U14") (pin "G13") (pinfunction "VDD_G13") (pintype "passive"))
      (node (ref "U14") (pin "G9") (pinfunction "VDD_G9") (pintype "passive"))
      (node (ref "U14") (pin "J13") (pinfunction "VDD_J13") (pintype "passive"))
      (node (ref "U14") (pin "J7") (pinfunction "VDD_J7") (pintype "passive"))
      (node (ref "U14") (pin "J9") (pinfunction "VDD_J9") (pintype "passive"))
      (node (ref "U14") (pin "K2") (pinfunction "VDD_PLL_K2") (pintype "passive"))
      (node (ref "U14") (pin "M5") (pinfunction "VDD_M5") (pintype "passive"))
      (node (ref "U14") (pin "N12") (pinfunction "VDD_N12") (pintype "passive"))
      (node (ref "U14") (pin "N7") (pinfunction "VDD_N7") (pintype "passive"))
      (node (ref "U14") (pin "N9") (pinfunction "VDD_N9") (pintype "passive"))
      (node (ref "U14") (pin "R12") (pinfunction "VDD_R12") (pintype "passive"))
      (node (ref "U14") (pin "R5") (pinfunction "VDD_R5") (pintype "passive"))
      (node (ref "U14") (pin "R7") (pinfunction "VDD_R7") (pintype "passive"))
      (node (ref "U14") (pin "R9") (pinfunction "VDD_R9") (pintype "passive"))
      (node (ref "U14") (pin "U7") (pinfunction "VDD_U7") (pintype "passive"))
      (node (ref "U14") (pin "V2") (pinfunction "VDD_ANA_V2") (pintype "passive"))
      (node (ref "U14") (pin "W11") (pinfunction "VDD_W11") (pintype "passive"))
      (node (ref "U14") (pin "Y18") (pinfunction "VDD_PLL2_Y18") (pintype "passive"))
    )
    (net (code "8") (name "VDD_ADC") (class "Default")
      (node (ref "C214") (pin "1") (pinfunction "1_1") (pintype "passive"))
      (node (ref "R133") (pin "2") (pinfunction "2_2") (pintype "passive"))
      (node (ref "U14") (pin "U8") (pinfunction "VDDA_U8") (pintype "passive"))
    )
    (net (code "9") (name "VDD_CORE") (class "Default")
      (node (ref "C124") (pin "2") (pinfunction "2_2") (pintype "passive"))
      (node (ref "C133") (pin "2") (pinfunction "2_2") (pintype "passive"))
      (node (ref "C188") (pin "2") (pinfunction "2_2") (pintype "passive"))
      (node (ref "C189") (pin "2") (pinfunction "2_2") (pintype "passive"))
      (node (ref "C195") (pin "1") (pinfunction "1_1") (pintype "passive"))
      (node (ref "C196") (pin "2") (pinfunction "2_2") (pintype "passive"))
      (node (ref "C199") (pin "2") (pinfunction "2_2") (pintype "passive"))
      (node (ref "C200") (pin "2") (pinfunction "2_2") (pintype "passive"))
      (node (ref "C203") (pin "1") (pinfunction "1_1") (pintype "passive"))
      (node (ref "C213") (pin "2") (pinfunction "2_2") (pintype "passive"))
      (node (ref "U14") (pin "G11") (pinfunction "VDD_CORE_G11") (pintype "passive"))
      (node (ref "U14") (pin "J11") (pinfunction "VDD_CORE_J11") (pintype "passive"))
      (node (ref "U14") (pin "J15") (pinfunction "VDD_CORE_J15") (pintype "passive"))
      (node (ref "U14") (pin "L13") (pinfunction "VDD_CORE_L13") (pintype "passive"))
      (node (ref "U14") (pin "L7") (pinfunction "VDD_CORE_L7") (pintype "passive"))
      (node (ref "U14") (pin "L9") (pinfunction "VDD_CORE_L9") (pintype "passive"))
      (node (ref "U14") (pin "N10") (pinfunction "VDD_CORE_N10") (pintype "passive"))
      (node (ref "U14") (pin "N13") (pinfunction "VDD_CORE_N13") (pintype "passive"))
      (node (ref "U14") (pin "N15") (pinfunction "VDD_CORE_N15") (pintype "passive"))
      (node (ref "U14") (pin "R10") (pinfunction "VDD_CORE_R10") (pintype "passive"))
      (node (ref "U14") (pin "R13") (pinfunction "VDD_CORE_R13") (pintype "passive"))
      (node (ref "U14") (pin "U12") (pinfunction "VDD_CORE_U12") (pintype "passive"))
      (node (ref "U14") (pin "U14") (pinfunction "VDD_CORE_U14") (pintype "passive"))
    )
    (net (code "10") (name "VDD_CPU") (class "Default")
      (node (ref "C174") (pin "2") (pinfunction "2_2") (pintype "passive"))
      (node (ref "C177") (pin "1") (pinfunction "1_1") (pintype "passive"))
      (node (ref "C183") (pin "2") (pinfunction "2_2") (pintype "passive"))
      (node (ref "C186") (pin "2") (pinfunction "2_2") (pintype "passive"))
      (node (ref "C187") (pin "2") (pinfunction "2_2") (pintype "passive"))
      (node (ref "C191") (pin "1") (pinfunction "1_1") (pintype "passive"))
      (node (ref "C194") (pin "2") (pinfunction "2_2") (pintype "passive"))
      (node (ref "C66") (pin "2") (pinfunction "2_2") (pintype "passive"))
      (node (ref "C72") (pin "2") (pinfunction "2_2") (pintype "passive"))
      (node (ref "U14") (pin "E10") (pinfunction "VDD_CPU_E10") (pintype "passive"))
      (node (ref "U14") (pin "E7") (pinfunction "VDD_CPU_E7") (pintype "passive"))
      (node (ref "U14") (pin "G10") (pinfunction "VDD_CPU_G10") (pintype "passive"))
      (node (ref "U14") (pin "G5") (pinfunction "VDD_CPU_G5") (pintype "passive"))
      (node (ref "U14") (pin "G7") (pinfunction "VDD_CPU_G7") (pintype "passive"))
      (node (ref "U14") (pin "K5") (pinfunction "VDD_CPU_K5") (pintype "passive"))
      (node (ref "U14") (pin "K7") (pinfunction "VDD_CPU_K7") (pintype "passive"))
    )
    (net (code "11") (name "VDD_DDR") (class "Default")
      (node (ref "C175") (pin "2") (pinfunction "2_2") (pintype "passive"))
      (node (ref "C182") (pin "2") (pinfunction "2_2") (pintype "passive"))
      (node (ref "C184") (pin "2") (pinfunction "2_2") (pintype "passive"))
      (node (ref "C192") (pin "2") (pinfunction "2_2") (pintype "passive"))
      (node (ref "C193") (pin "2") (pinfunction "2_2") (pintype "passive"))
      (node (ref "C198") (pin "2") (pinfunction "2_2") (pintype "passive"))
      (node (ref "C204") (pin "1") (pinfunction "1_1") (pintype "passive"))
      (node (ref "C206") (pin "2") (pinfunction "2_2") (pintype "passive"))
      (node (ref "C211") (pin "2") (pinfunction "2_2") (pintype "passive"))
      (node (ref "C212") (pin "2") (pinfunction "2_2") (pintype "passive"))
      (node (ref "U14") (pin "E15") (pinfunction "VDDQ_DDR_E15") (pintype "passive"))
      (node (ref "U14") (pin "G15") (pinfunction "VDDQ_DDR_G15") (pintype "passive"))
      (node (ref "U14") (pin "G17") (pinfunction "VDDQ_DDR_G17") (pintype "passive"))
      (node (ref "U14") (pin "K15") (pinfunction "VDDQ_DDR_K15") (pintype "passive"))
      (node (ref "U14") (pin "K17") (pinfunction "VDDQ_DDR_K17") (pintype "passive"))
      (node (ref "U14") (pin "M15") (pinfunction "VDDQ_DDR_M15") (pintype "passive"))
      (node (ref "U14") (pin "M17") (pinfunction "VDDQ_DDR_M17") (pintype "passive"))
      (node (ref "U14") (pin "R15") (pinfunction "VDDQ_DDR_R15") (pintype "passive"))
      (node (ref "U14") (pin "R17") (pinfunction "VDDQ_DDR_R17") (pintype "passive"))
      (node (ref "U14") (pin "U15") (pinfunction "VDDQ_DDR_U15") (pintype "passive"))
    )
    (net (code "12") (name "VDD_USB") (class "Default")
      (node (ref "C119") (pin "2") (pinfunction "2_2") (pintype "passive"))
      (node (ref "U14") (pin "W14") (pinfunction "VDD3V3_USBHS_W14") (pintype "passive"))
    )
  )
)
